# Balancing.net
KiCad netlist of a schematic drawn in Altium Designer
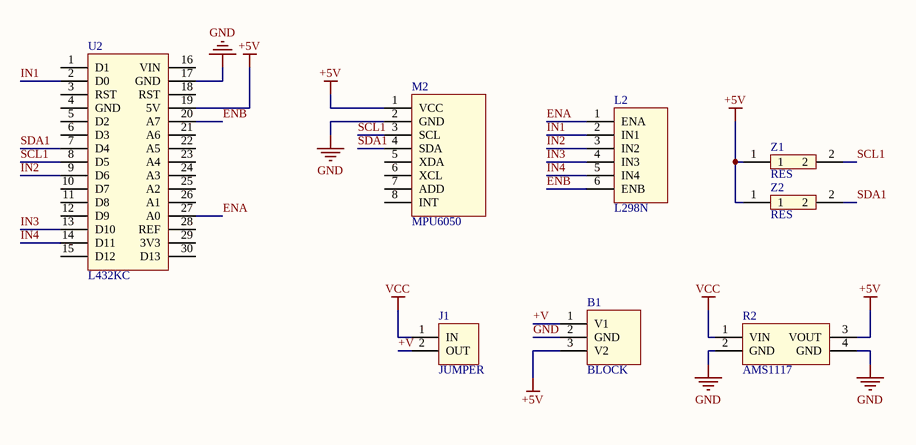
[diagram p0: Balancing.SchDoc]

(export (version "E")
  (design (tool "Eeschema 10.0.6"))
  (components
    (comp (ref "B1") (value "BLOCK") (footprint "BLOCK") (libsource (lib "Balancing") (part "BLOCK")))
    (comp (ref "J1") (value "JUMPER") (footprint "JUMPER") (libsource (lib "Balancing") (part "JUMPER")))
    (comp (ref "L2") (value "L298N") (footprint "L298N") (libsource (lib "Balancing") (part "L298N")))
    (comp (ref "M2") (value "MPU6050") (footprint "MPU6050") (libsource (lib "Balancing") (part "MPU6050")))
    (comp (ref "R2") (value "AMS1117") (footprint "AMS1117") (libsource (lib "Balancing") (part "AMS1117")))
    (comp (ref "U2") (value "L432KC") (footprint "L432KC") (libsource (lib "Balancing") (part "L432KC")))
    (comp (ref "Z1") (value "RES") (footprint "RES") (libsource (lib "Balancing") (part "RES")))
    (comp (ref "Z2") (value "RES") (footprint "RES") (libsource (lib "Balancing") (part "RES")))
  )
  (nets
    (net (code "1") (name "+5V") (class "Default")
      (node (ref "B1") (pin "3") (pinfunction "V2_3") (pintype "passive"))
      (node (ref "M2") (pin "1") (pinfunction "VCC_1") (pintype "passive"))
      (node (ref "R2") (pin "3") (pinfunction "VOUT_3") (pintype "passive"))
      (node (ref "U2") (pin "19") (pinfunction "5V_19") (pintype "passive"))
      (node (ref "Z1") (pin "1") (pinfunction "1_1") (pintype "passive"))
      (node (ref "Z2") (pin "1") (pinfunction "1_1") (pintype "passive"))
    )
    (net (code "2") (name "/+V") (class "Default")
      (node (ref "B1") (pin "1") (pinfunction "V1_1") (pintype "passive"))
      (node (ref "J1") (pin "2") (pinfunction "OUT_2") (pintype "passive"))
    )
    (net (code "3") (name "/ENA") (class "Default")
      (node (ref "L2") (pin "1") (pinfunction "ENA_1") (pintype "passive"))
      (node (ref "U2") (pin "27") (pinfunction "A0_27") (pintype "passive"))
    )
    (net (code "4") (name "/ENB") (class "Default")
      (node (ref "L2") (pin "6") (pinfunction "ENB_6") (pintype "passive"))
      (node (ref "U2") (pin "20") (pinfunction "A7_20") (pintype "passive"))
    )
    (net (code "5") (name "/IN1") (class "Default")
      (node (ref "L2") (pin "2") (pinfunction "IN1_2") (pintype "passive"))
      (node (ref "U2") (pin "2") (pinfunction "D0_2") (pintype "passive"))
    )
    (net (code "6") (name "/IN2") (class "Default")
      (node (ref "L2") (pin "3") (pinfunction "IN2_3") (pintype "passive"))
      (node (ref "U2") (pin "9") (pinfunction "D6_9") (pintype "passive"))
    )
    (net (code "7") (name "/IN3") (class "Default")
      (node (ref "L2") (pin "4") (pinfunction "IN3_4") (pintype "passive"))
      (node (ref "U2") (pin "13") (pinfunction "D10_13") (pintype "passive"))
    )
    (net (code "8") (name "/IN4") (class "Default")
      (node (ref "L2") (pin "5") (pinfunction "IN4_5") (pintype "passive"))
      (node (ref "U2") (pin "14") (pinfunction "D11_14") (pintype "passive"))
    )
    (net (code "9") (name "/SCL1") (class "Default")
      (node (ref "M2") (pin "3") (pinfunction "SCL_3") (pintype "passive"))
      (node (ref "U2") (pin "8") (pinfunction "D5_8") (pintype "passive"))
      (node (ref "Z1") (pin "2") (pinfunction "2_2") (pintype "passive"))
    )
    (net (code "10") (name "/SDA1") (class "Default")
      (node (ref "M2") (pin "4") (pinfunction "SDA_4") (pintype "passive"))
      (node (ref "U2") (pin "7") (pinfunction "D4_7") (pintype "passive"))
      (node (ref "Z2") (pin "2") (pinfunction "2_2") (pintype "passive"))
    )
    (net (code "11") (name "GND") (class "Default")
      (node (ref "B1") (pin "2") (pinfunction "GND_2") (pintype "passive"))
      (node (ref "M2") (pin "2") (pinfunction "GND_2") (pintype "passive"))
      (node (ref "R2") (pin "2") (pinfunction "GND_2") (pintype "passive"))
      (node (ref "R2") (pin "4") (pinfunction "GND_4") (pintype "passive"))
      (node (ref "U2") (pin "17") (pinfunction "GND_17") (pintype "passive"))
    )
    (net (code "12") (name "VCC") (class "Default")
      (node (ref "J1") (pin "1") (pinfunction "IN_1") (pintype "passive"))
      (node (ref "R2") (pin "1") (pinfunction "VIN_1") (pintype "passive"))
    )
    (net (code "13") (name "unconnected-(M2-ADD-Pad7)") (class "Default")
      (node (ref "M2") (pin "7") (pinfunction "ADD_7") (pintype "passive"))
    )
    (net (code "14") (name "unconnected-(M2-INT-Pad8)") (class "Default")
      (node (ref "M2") (pin "8") (pinfunction "INT_8") (pintype "passive"))
    )
    (net (code "15") (name "unconnected-(M2-XCL-Pad6)") (class "Default")
      (node (ref "M2") (pin "6") (pinfunction "XCL_6") (pintype "passive"))
    )
    (net (code "16") (name "unconnected-(M2-XDA-Pad5)") (class "Default")
      (node (ref "M2") (pin "5") (pinfunction "XDA_5") (pintype "passive"))
    )
    (net (code "17") (name "unconnected-(U2-3V3-Pad29)") (class "Default")
      (node (ref "U2") (pin "29") (pinfunction "3V3_29") (pintype "passive"))
    )
    (net (code "18") (name "unconnected-(U2-A1-Pad26)") (class "Default")
      (node (ref "U2") (pin "26") (pinfunction "A1_26") (pintype "passive"))
    )
    (net (code "19") (name "unconnected-(U2-A2-Pad25)") (class "Default")
      (node (ref "U2") (pin "25") (pinfunction "A2_25") (pintype "passive"))
    )
    (net (code "20") (name "unconnected-(U2-A3-Pad24)") (class "Default")
      (node (ref "U2") (pin "24") (pinfunction "A3_24") (pintype "passive"))
    )
    (net (code "21") (name "unconnected-(U2-A4-Pad23)") (class "Default")
      (node (ref "U2") (pin "23") (pinfunction "A4_23") (pintype "passive"))
    )
    (net (code "22") (name "unconnected-(U2-A5-Pad22)") (class "Default")
      (node (ref "U2") (pin "22") (pinfunction "A5_22") (pintype "passive"))
    )
    (net (code "23") (name "unconnected-(U2-A6-Pad21)") (class "Default")
      (node (ref "U2") (pin "21") (pinfunction "A6_21") (pintype "passive"))
    )
    (net (code "24") (name "unconnected-(U2-D1-Pad1)") (class "Default")
      (node (ref "U2") (pin "1") (pinfunction "D1_1") (pintype "passive"))
    )
    (net (code "25") (name "unconnected-(U2-D2-Pad5)") (class "Default")
      (node (ref "U2") (pin "5") (pinfunction "D2_5") (pintype "passive"))
    )
    (net (code "26") (name "unconnected-(U2-D3-Pad6)") (class "Default")
      (node (ref "U2") (pin "6") (pinfunction "D3_6") (pintype "passive"))
    )
    (net (code "27") (name "unconnected-(U2-D7-Pad10)") (class "Default")
      (node (ref "U2") (pin "10") (pinfunction "D7_10") (pintype "passive"))
    )
    (net (code "28") (name "unconnected-(U2-D8-Pad11)") (class "Default")
      (node (ref "U2") (pin "11") (pinfunction "D8_11") (pintype "passive"))
    )
    (net (code "29") (name "unconnected-(U2-D9-Pad12)") (class "Default")
      (node (ref "U2") (pin "12") (pinfunction "D9_12") (pintype "passive"))
    )
    (net (code "30") (name "unconnected-(U2-D12-Pad15)") (class "Default")
      (node (ref "U2") (pin "15") (pinfunction "D12_15") (pintype "passive"))
    )
    (net (code "31") (name "unconnected-(U2-D13-Pad30)") (class "Default")
      (node (ref "U2") (pin "30") (pinfunction "D13_30") (pintype "passive"))
    )
    (net (code "32") (name "unconnected-(U2-GND-Pad4)") (class "Default")
      (node (ref "U2") (pin "4") (pinfunction "GND_4") (pintype "passive"))
    )
    (net (code "33") (name "unconnected-(U2-REF-Pad28)") (class "Default")
      (node (ref "U2") (pin "28") (pinfunction "REF_28") (pintype "passive"))
    )
    (net (code "34") (name "unconnected-(U2-RST-Pad3)") (class "Default")
      (node (ref "U2") (pin "3") (pinfunction "RST_3") (pintype "passive"))
    )
    (net (code "35") (name "unconnected-(U2-RST-Pad18)") (class "Default")
      (node (ref "U2") (pin "18") (pinfunction "RST_18") (pintype "passive"))
    )
    (net (code "36") (name "unconnected-(U2-VIN-Pad16)") (class "Default")
      (node (ref "U2") (pin "16") (pinfunction "VIN_16") (pintype "passive"))
    )
  )
)
